# RCU_PCB.net
KiCad netlist of a schematic drawn in EAGLE
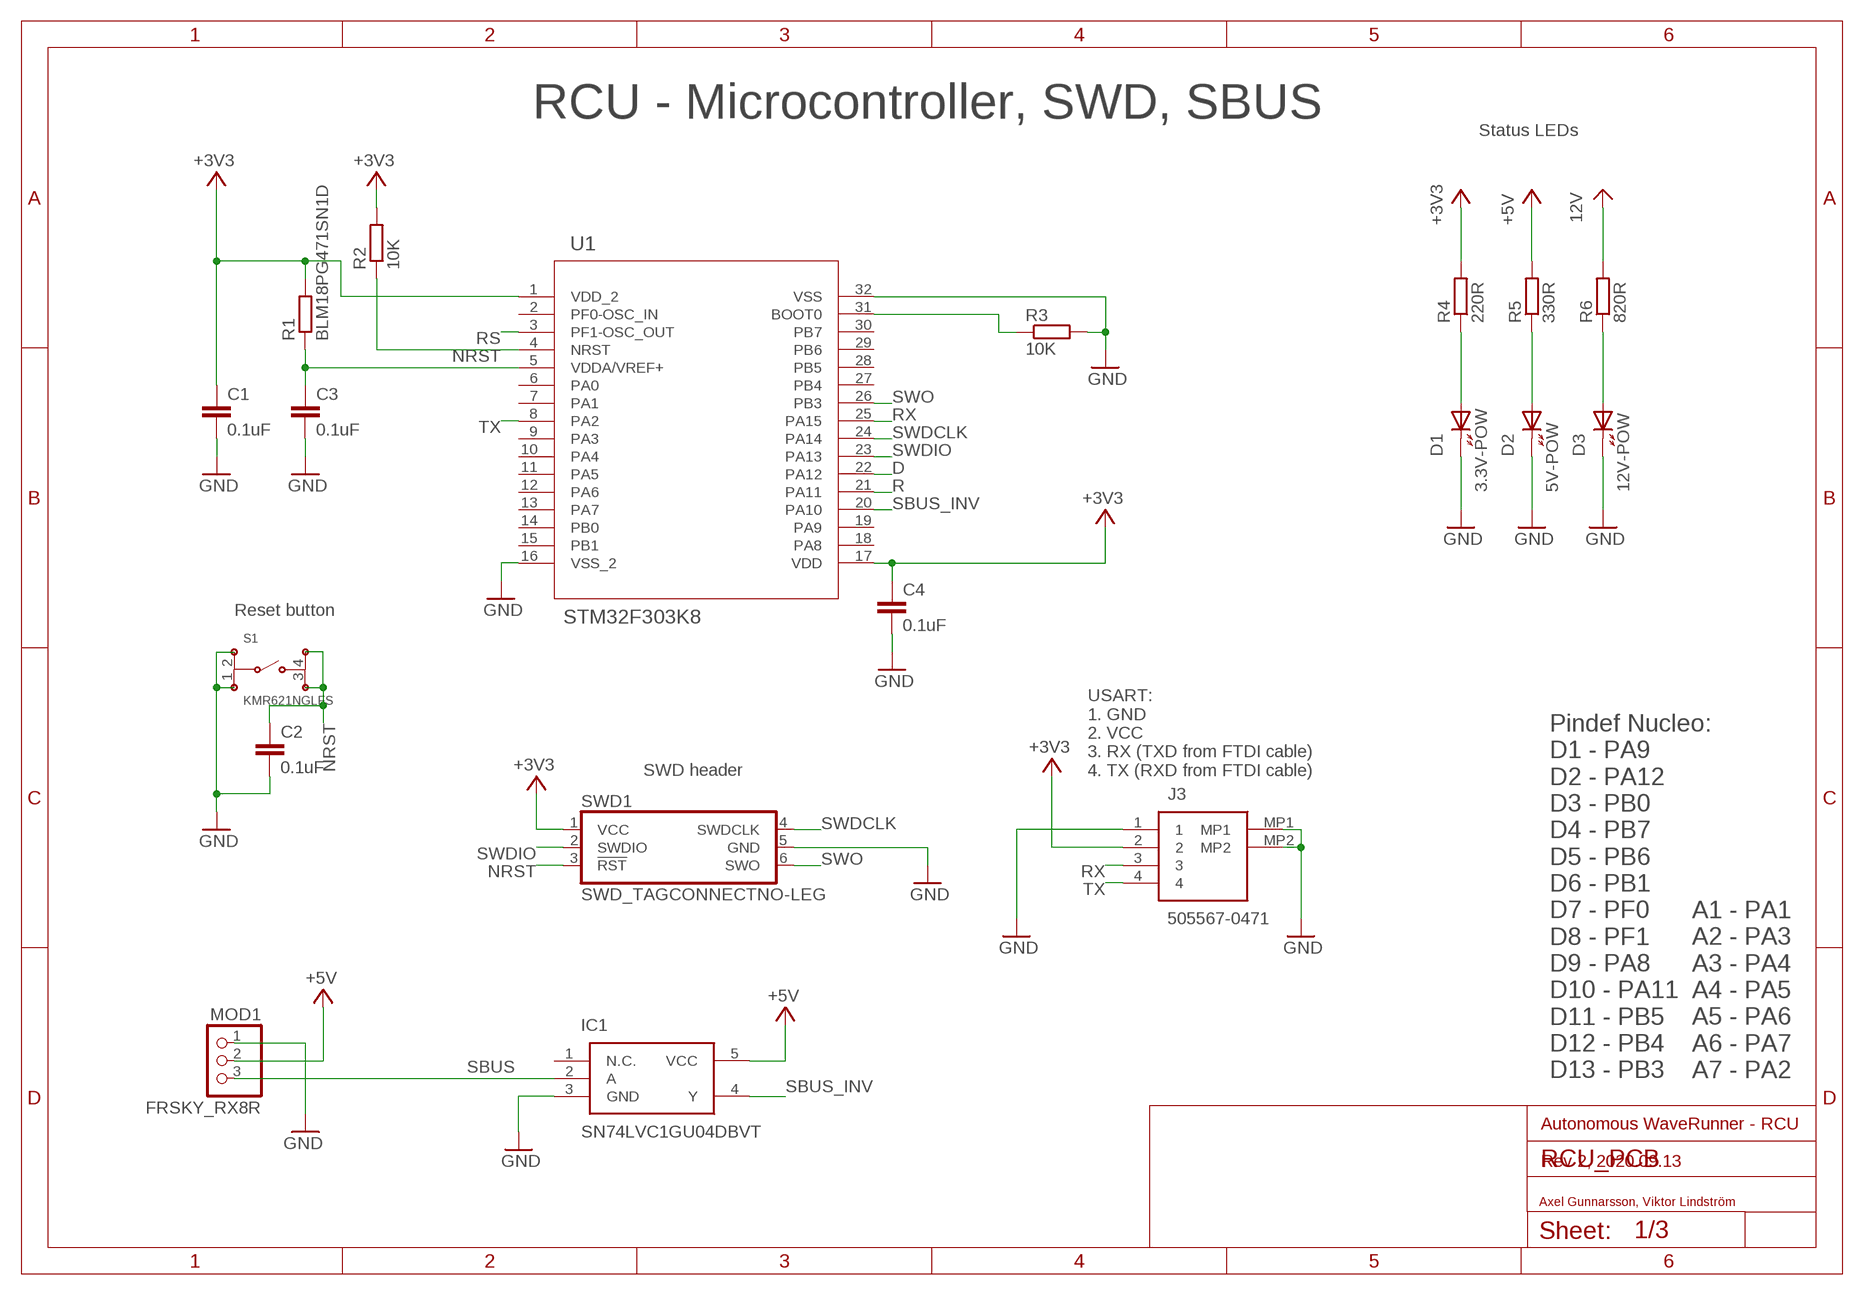
[diagram p0: schematic, sheet 1]
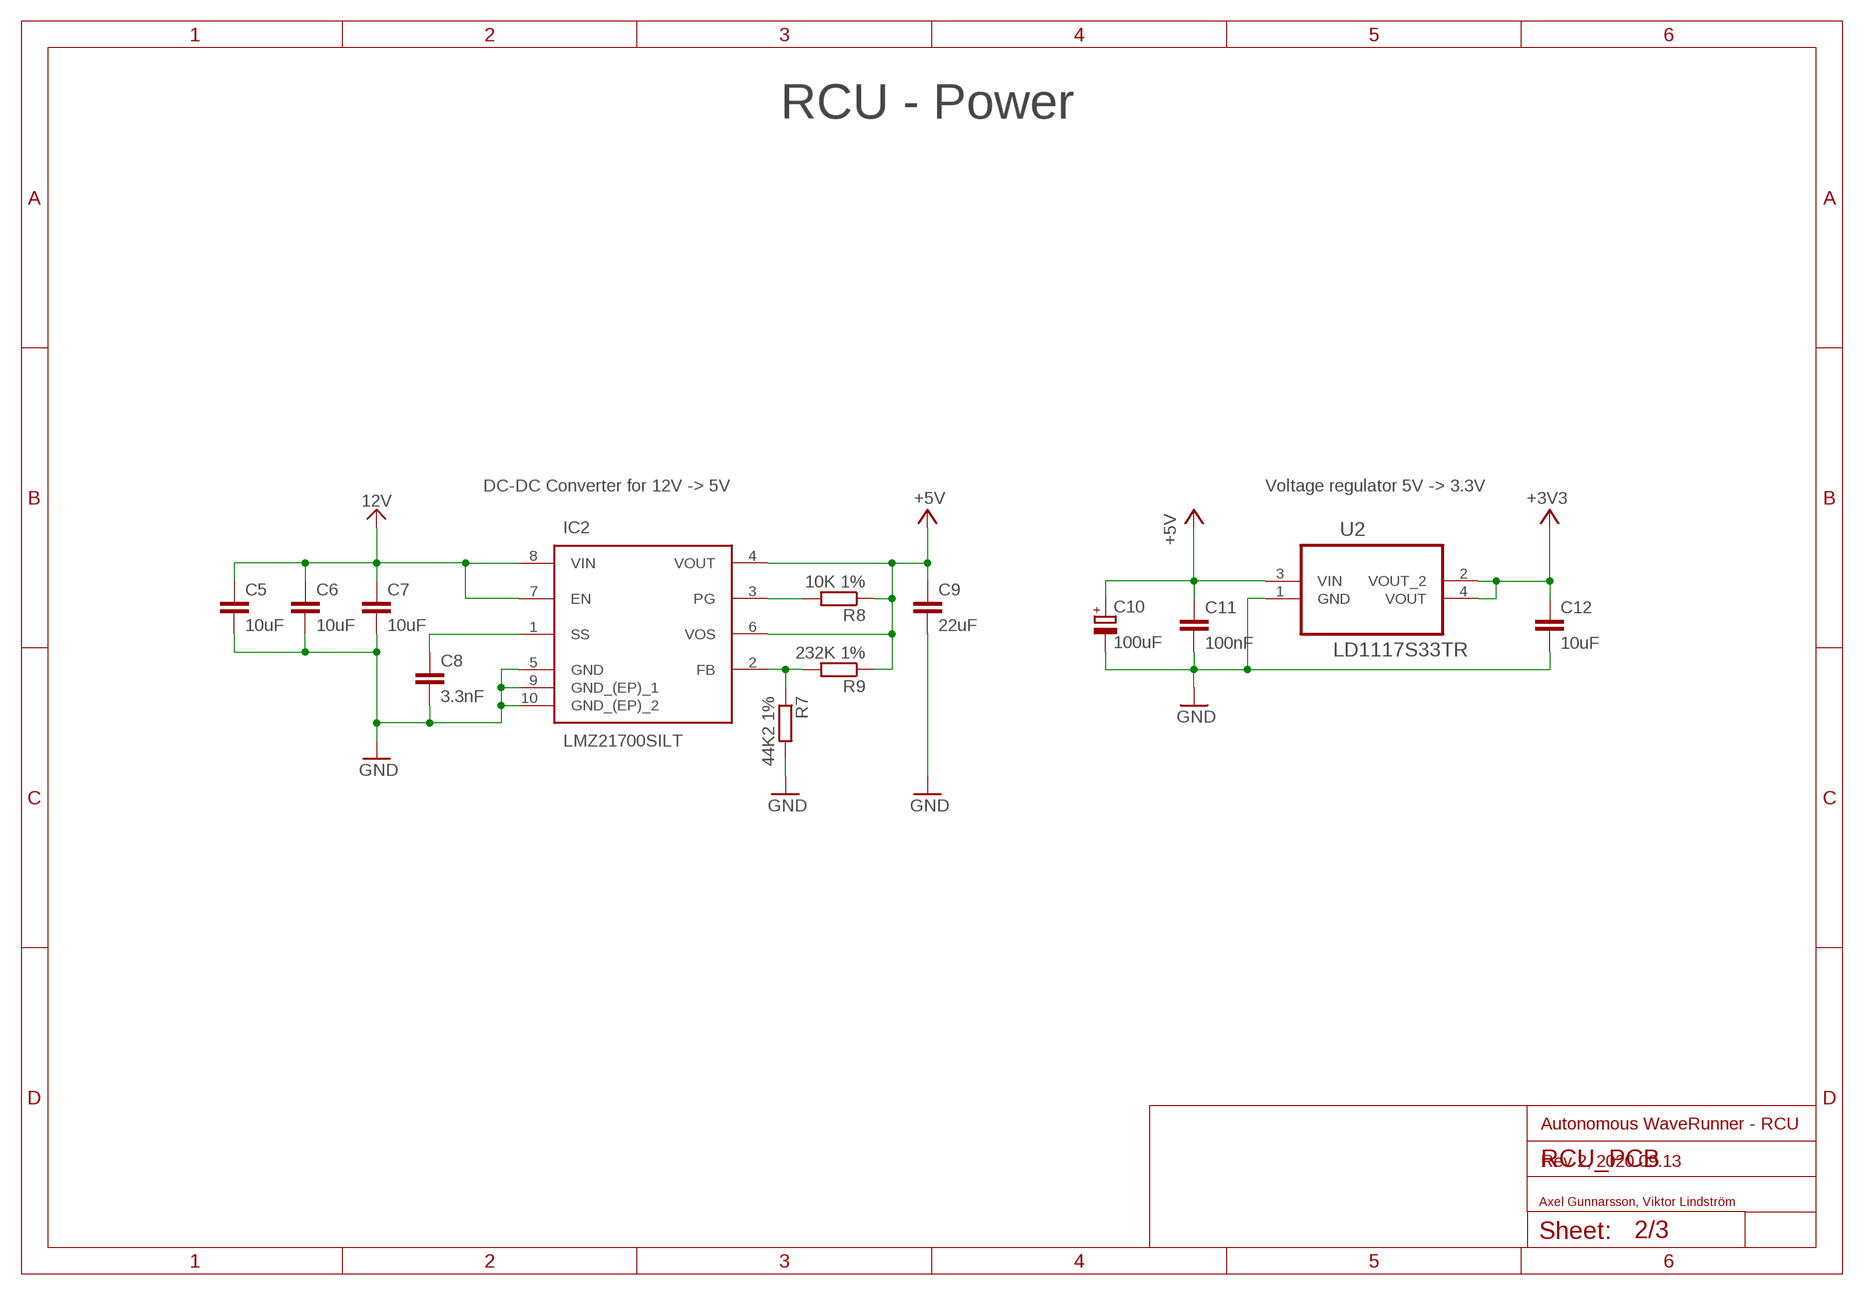
[diagram p1: schematic, sheet 2]
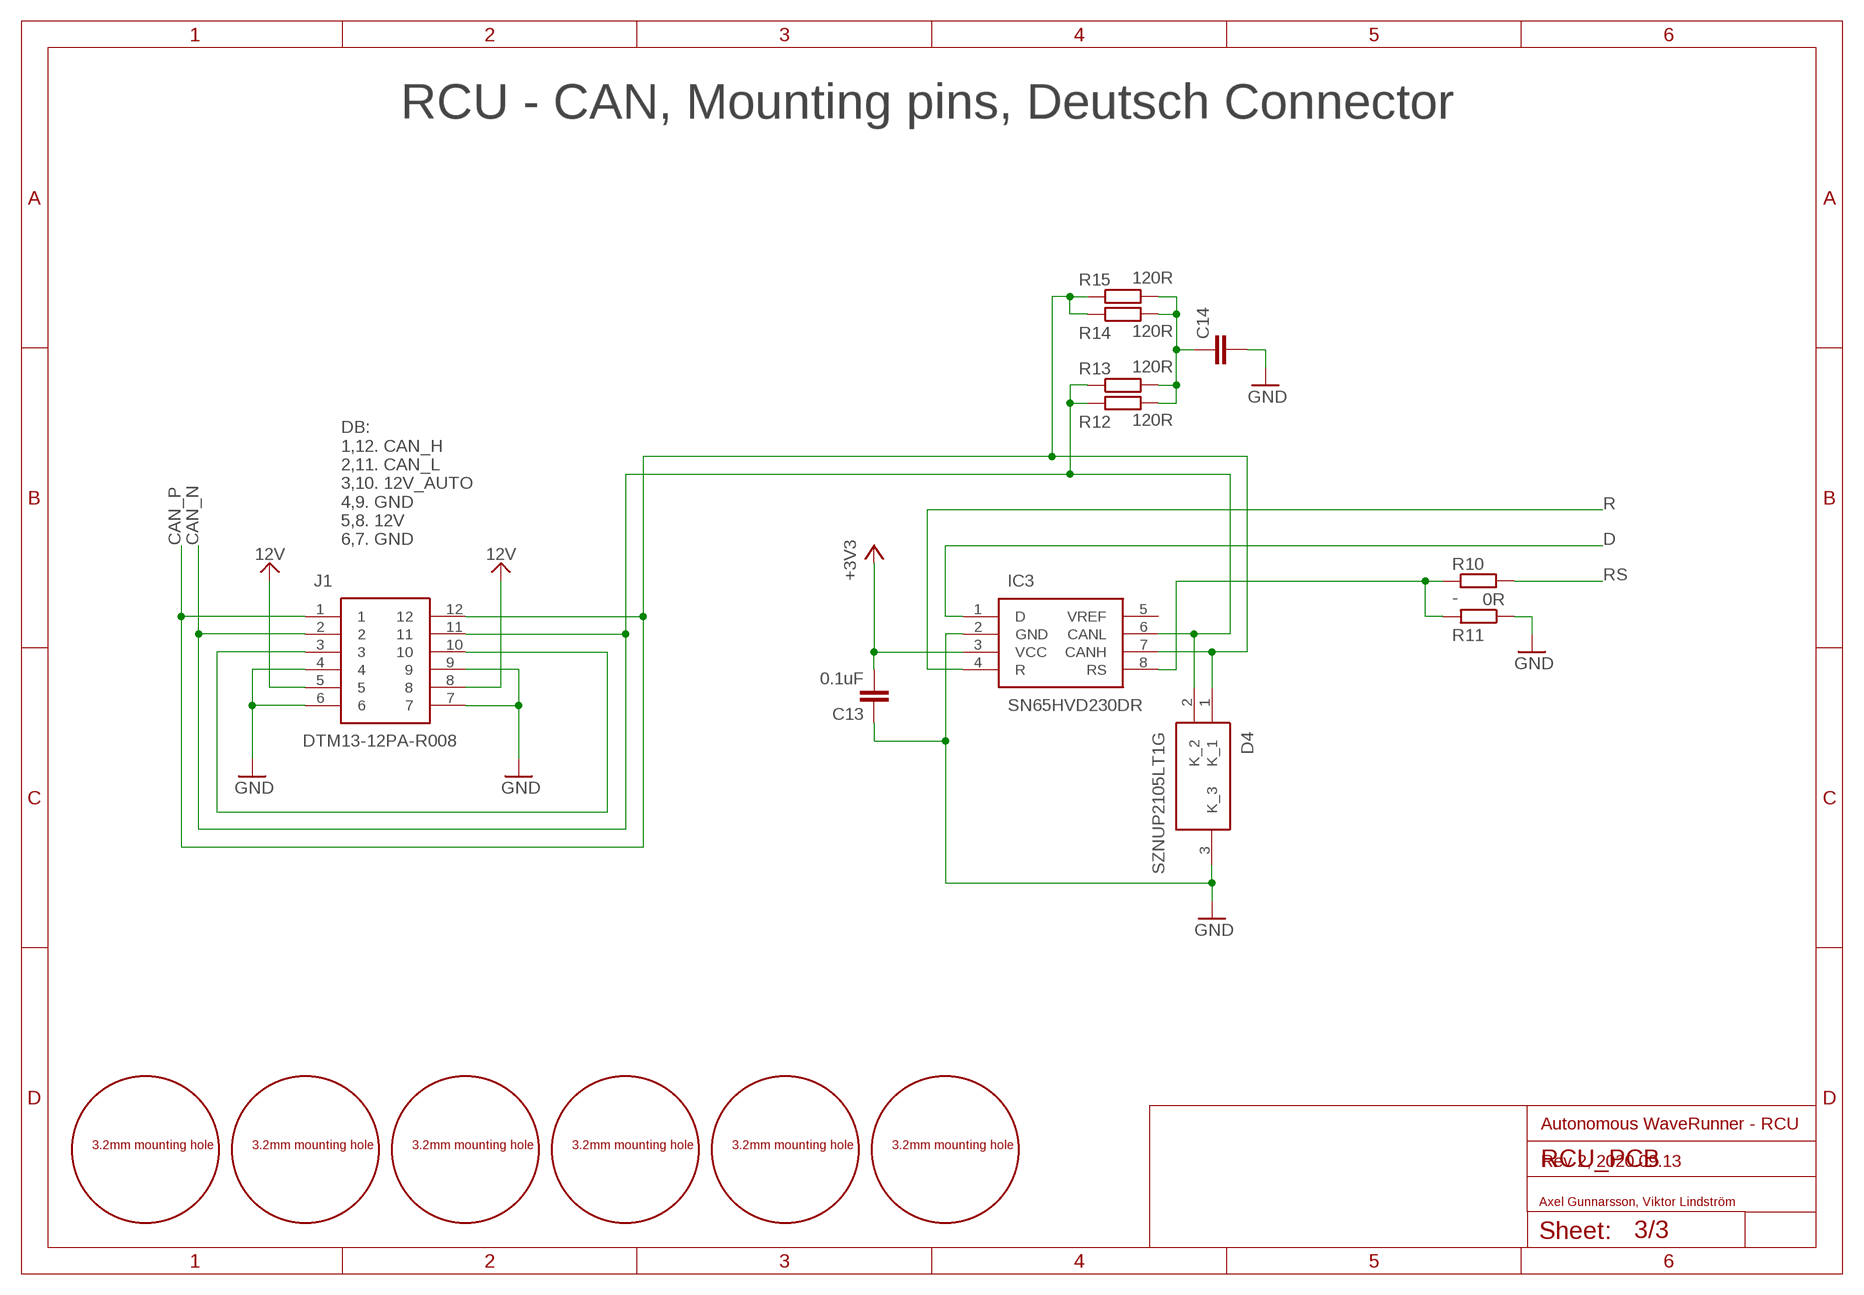
[diagram p2: schematic, sheet 3]

(export (version "E")
  (design (tool "Eeschema 10.0.6"))
  (components
    (comp (ref "C13")
      (value "0.1uF")
      (footprint "eagle-import:C0603")
      (libsource (lib "eagle-import") (part "C0603"))
    )
    (comp (ref "C14")
      (value "C0805")
      (footprint "eagle-import:C0805")
      (libsource (lib "eagle-import") (part "C0805"))
    )
    (comp (ref "D4")
      (value "SZNUP2105LT1G")
      (footprint "eagle-import:SOT96P237X111-3N")
      (fields (field (name "MOUSER_PART_NUMBER") "863-SZNUP2105LT1G"))
      (libsource (lib "eagle-import") (part "SZNUP2105LT1G"))
    )
    (comp (ref "HOLE1")
      (value "M3_MOUNTING_HOLE")
      (footprint "eagle-import:M3_MOUNTING_HOLE")
      (libsource (lib "eagle-import") (part "M3_MOUNTING_HOLE"))
    )
    (comp (ref "HOLE2")
      (value "M3_MOUNTING_HOLE")
      (footprint "eagle-import:M3_MOUNTING_HOLE")
      (libsource (lib "eagle-import") (part "M3_MOUNTING_HOLE"))
    )
    (comp (ref "HOLE3")
      (value "M3_MOUNTING_HOLE")
      (footprint "eagle-import:M3_MOUNTING_HOLE")
      (libsource (lib "eagle-import") (part "M3_MOUNTING_HOLE"))
    )
    (comp (ref "HOLE4")
      (value "M3_MOUNTING_HOLE")
      (footprint "eagle-import:M3_MOUNTING_HOLE")
      (libsource (lib "eagle-import") (part "M3_MOUNTING_HOLE"))
    )
    (comp (ref "HOLE5")
      (value "M3_MOUNTING_HOLE")
      (footprint "eagle-import:M3_MOUNTING_HOLE")
      (fields (field (name "SPICEPREFIX") "X"))
      (libsource (lib "eagle-import") (part "M3_MOUNTING_HOLE"))
    )
    (comp (ref "HOLE6")
      (value "M3_MOUNTING_HOLE")
      (footprint "eagle-import:M3_MOUNTING_HOLE")
      (fields (field (name "SPICEPREFIX") "X"))
      (libsource (lib "eagle-import") (part "M3_MOUNTING_HOLE"))
    )
    (comp (ref "IC3")
      (value "SN65HVD230DR")
      (footprint "eagle-import:SOT127P600X175-8N")
      (fields (field (name "MOUSER_PART_NUMBER") "595-SN65HVD230DR"))
      (libsource (lib "eagle-import") (part "SN65HVD230DR"))
    )
    (comp (ref "J1")
      (value "DTM13-12PA-R008")
      (footprint "eagle-import:DTM1312PAR008")
      (fields (field (name "RS_PART_NUMBER") "7242563"))
      (libsource (lib "eagle-import") (part "DTM13-12PA-R008"))
    )
    (comp (ref "R10")
      (value "-")
      (footprint "eagle-import:R0603")
      (libsource (lib "eagle-import") (part "R0603"))
    )
    (comp (ref "R11")
      (value "0R")
      (footprint "eagle-import:R0603")
      (libsource (lib "eagle-import") (part "R0603"))
    )
    (comp (ref "R12")
      (value "120R")
      (footprint "eagle-import:R1210")
      (libsource (lib "eagle-import") (part "R-EU_R1210"))
    )
    (comp (ref "R13")
      (value "120R")
      (footprint "eagle-import:R1210")
      (libsource (lib "eagle-import") (part "R-EU_R1210"))
    )
    (comp (ref "R14")
      (value "120R")
      (footprint "eagle-import:R1210")
      (libsource (lib "eagle-import") (part "R-EU_R1210"))
    )
    (comp (ref "R15")
      (value "120R")
      (footprint "eagle-import:R1210")
      (libsource (lib "eagle-import") (part "R-EU_R1210"))
    )
    (comp (ref "C1")
      (value "0.1uF")
      (footprint "eagle-import:C0603")
      (libsource (lib "eagle-import") (part "C0603"))
    )
    (comp (ref "C2")
      (value "0.1uF")
      (footprint "eagle-import:C0603")
      (libsource (lib "eagle-import") (part "C0603"))
    )
    (comp (ref "C3")
      (value "0.1uF")
      (footprint "eagle-import:C0603")
      (libsource (lib "eagle-import") (part "C0603"))
    )
    (comp (ref "C4")
      (value "0.1uF")
      (footprint "eagle-import:C0603")
      (libsource (lib "eagle-import") (part "C0603"))
    )
    (comp (ref "D1")
      (value "3.3V-POW")
      (footprint "eagle-import:CHIP-LED0805")
      (libsource (lib "eagle-import") (part "CHIP-LED0805"))
    )
    (comp (ref "D2")
      (value "5V-POW")
      (footprint "eagle-import:CHIP-LED0805")
      (libsource (lib "eagle-import") (part "CHIP-LED0805"))
    )
    (comp (ref "D3")
      (value "12V-POW")
      (footprint "eagle-import:CHIP-LED0805")
      (libsource (lib "eagle-import") (part "CHIP-LED0805"))
    )
    (comp (ref "IC1")
      (value "SN74LVC1GU04DBVT")
      (footprint "eagle-import:SOT95P280X145-5N")
      (fields (field (name "RS_PART_NUMBER") "7968253P"))
      (libsource (lib "eagle-import") (part "SN74LVC1GU04DBVT"))
    )
    (comp (ref "J3")
      (value "505567-0471")
      (footprint "eagle-import:5055680471")
      (libsource (lib "eagle-import") (part "505567-0471"))
    )
    (comp (ref "MOD1")
      (value "FRSKY_RX8R")
      (footprint "eagle-import:FRSKY_RX8R")
      (libsource (lib "eagle-import") (part "FRSKY_RX8R"))
    )
    (comp (ref "R1")
      (value "BLM18PG471SN1D")
      (footprint "eagle-import:R0603")
      (libsource (lib "eagle-import") (part "R0603"))
    )
    (comp (ref "R2")
      (value "10K")
      (footprint "eagle-import:R0603")
      (libsource (lib "eagle-import") (part "R0603"))
    )
    (comp (ref "R3")
      (value "10K")
      (footprint "eagle-import:R0603")
      (libsource (lib "eagle-import") (part "R0603"))
    )
    (comp (ref "R4")
      (value "220R")
      (footprint "eagle-import:R0603")
      (libsource (lib "eagle-import") (part "R0603"))
    )
    (comp (ref "R5")
      (value "330R")
      (footprint "eagle-import:R0603")
      (libsource (lib "eagle-import") (part "R0603"))
    )
    (comp (ref "R6")
      (value "820R")
      (footprint "eagle-import:R0603")
      (libsource (lib "eagle-import") (part "R0603"))
    )
    (comp (ref "S1")
      (value "KMR621NGLFS")
      (footprint "eagle-import:KMR621NGLFS")
      (libsource (lib "eagle-import") (part "KMR621NGLFS"))
    )
    (comp (ref "SWD1")
      (value "SWD_TAGCONNECTNO-LEG")
      (footprint "eagle-import:TC2030-IDC-NL")
      (libsource (lib "eagle-import") (part "SWD_TAGCONNECTNO-LEG"))
    )
    (comp (ref "U1")
      (value "STM32F303K8")
      (footprint "eagle-import:LQFP-32")
      (fields (field (name "MANUFACTURER_PART_NUMBER") "stm32f303_334kxt"))
      (libsource (lib "eagle-import") (part "STM32F303K8"))
    )
    (comp (ref "C5")
      (value "10uF")
      (footprint "eagle-import:C1206")
      (libsource (lib "eagle-import") (part "C1206"))
    )
    (comp (ref "C6")
      (value "10uF")
      (footprint "eagle-import:C1206")
      (libsource (lib "eagle-import") (part "C1206"))
    )
    (comp (ref "C7")
      (value "10uF")
      (footprint "eagle-import:C1206")
      (libsource (lib "eagle-import") (part "C1206"))
    )
    (comp (ref "C8")
      (value "3.3nF")
      (footprint "eagle-import:C0603")
      (libsource (lib "eagle-import") (part "C0603"))
    )
    (comp (ref "C9")
      (value "22uF")
      (footprint "eagle-import:C0805")
      (libsource (lib "eagle-import") (part "C0805"))
    )
    (comp (ref "C10")
      (value "100uF")
      (footprint "eagle-import:PANASONIC_C")
      (libsource (lib "eagle-import") (part "PANASONIC_C"))
    )
    (comp (ref "C11")
      (value "100nF")
      (footprint "eagle-import:C0603")
      (libsource (lib "eagle-import") (part "C0603"))
    )
    (comp (ref "C12")
      (value "10uF")
      (footprint "eagle-import:C0805")
      (libsource (lib "eagle-import") (part "C0805"))
    )
    (comp (ref "IC2")
      (value "LMZ21700SILT")
      (footprint "eagle-import:SIL0008E")
      (fields (field (name "RS_PART_NUMBER") "9009750P"))
      (libsource (lib "eagle-import") (part "LMZ21700SILT"))
    )
    (comp (ref "R7")
      (value "44K2 1%")
      (footprint "eagle-import:R0603")
      (libsource (lib "eagle-import") (part "R0603"))
    )
    (comp (ref "R8")
      (value "10K 1%")
      (footprint "eagle-import:R0603")
      (libsource (lib "eagle-import") (part "R0603"))
    )
    (comp (ref "R9")
      (value "232K 1%")
      (footprint "eagle-import:R0603")
      (libsource (lib "eagle-import") (part "R0603"))
    )
    (comp (ref "U2")
      (value "LD1117S33TR")
      (footprint "eagle-import:SOT230P700X180-4N")
      (libsource (lib "eagle-import") (part "LD1117S33TR"))
    )
  )
  (nets
    (net (code "1") (name "+3V3") (class "Default")
      (node (ref "C1") (pin "1") (pinfunction "1_1") (pintype "passive"))
      (node (ref "C12") (pin "1") (pinfunction "1_1") (pintype "passive"))
      (node (ref "C13") (pin "2") (pinfunction "2_2") (pintype "passive"))
      (node (ref "C4") (pin "1") (pinfunction "1_1") (pintype "passive"))
      (node (ref "IC3") (pin "3") (pinfunction "VCC_3") (pintype "bidirectional"))
      (node (ref "J3") (pin "2") (pinfunction "2_2") (pintype "bidirectional"))
      (node (ref "R1") (pin "2") (pinfunction "2_2") (pintype "passive"))
      (node (ref "R2") (pin "2") (pinfunction "2_2") (pintype "passive"))
      (node (ref "R4") (pin "2") (pinfunction "2_2") (pintype "passive"))
      (node (ref "SWD1") (pin "1") (pinfunction "VCC_1") (pintype "passive"))
      (node (ref "U1") (pin "1") (pinfunction "VDD_2_1") (pintype "power_in"))
      (node (ref "U1") (pin "17") (pinfunction "VDD_17") (pintype "power_in"))
      (node (ref "U2") (pin "2") (pinfunction "VOUT_2_2") (pintype "output"))
      (node (ref "U2") (pin "4") (pinfunction "VOUT_4") (pintype "output"))
    )
    (net (code "2") (name "+5V") (class "Default")
      (node (ref "C10") (pin "+") (pinfunction "+_+") (pintype "passive"))
      (node (ref "C11") (pin "1") (pinfunction "1_1") (pintype "passive"))
      (node (ref "C9") (pin "1") (pinfunction "1_1") (pintype "passive"))
      (node (ref "IC1") (pin "5") (pinfunction "VCC_5") (pintype "bidirectional"))
      (node (ref "IC2") (pin "4") (pinfunction "VOUT_4") (pintype "output"))
      (node (ref "IC2") (pin "6") (pinfunction "VOS_6") (pintype "bidirectional"))
      (node (ref "MOD1") (pin "2") (pinfunction "2_2") (pintype "passive"))
      (node (ref "R5") (pin "2") (pinfunction "2_2") (pintype "passive"))
      (node (ref "R8") (pin "1") (pinfunction "1_1") (pintype "passive"))
      (node (ref "R9") (pin "1") (pinfunction "1_1") (pintype "passive"))
      (node (ref "U2") (pin "3") (pinfunction "VIN_3") (pintype "input"))
    )
    (net (code "3") (name "12V") (class "Default")
      (node (ref "C5") (pin "1") (pinfunction "1_1") (pintype "passive"))
      (node (ref "C6") (pin "1") (pinfunction "1_1") (pintype "passive"))
      (node (ref "C7") (pin "1") (pinfunction "1_1") (pintype "passive"))
      (node (ref "IC2") (pin "7") (pinfunction "EN_7") (pintype "bidirectional"))
      (node (ref "IC2") (pin "8") (pinfunction "VIN_8") (pintype "input"))
      (node (ref "J1") (pin "5") (pinfunction "5_5") (pintype "bidirectional"))
      (node (ref "J1") (pin "8") (pinfunction "8_8") (pintype "bidirectional"))
      (node (ref "R6") (pin "2") (pinfunction "2_2") (pintype "passive"))
    )
    (net (code "4") (name "CAN_N") (class "Default")
      (node (ref "D4") (pin "2") (pinfunction "K_2_2") (pintype "bidirectional"))
      (node (ref "IC3") (pin "6") (pinfunction "CANL_6") (pintype "bidirectional"))
      (node (ref "J1") (pin "11") (pinfunction "11_11") (pintype "bidirectional"))
      (node (ref "J1") (pin "2") (pinfunction "2_2") (pintype "bidirectional"))
      (node (ref "R12") (pin "1") (pinfunction "1_1") (pintype "passive"))
      (node (ref "R13") (pin "1") (pinfunction "1_1") (pintype "passive"))
    )
    (net (code "5") (name "CAN_P") (class "Default")
      (node (ref "D4") (pin "1") (pinfunction "K_1_1") (pintype "bidirectional"))
      (node (ref "IC3") (pin "7") (pinfunction "CANH_7") (pintype "bidirectional"))
      (node (ref "J1") (pin "1") (pinfunction "1_1") (pintype "bidirectional"))
      (node (ref "J1") (pin "12") (pinfunction "12_12") (pintype "bidirectional"))
      (node (ref "R14") (pin "1") (pinfunction "1_1") (pintype "passive"))
      (node (ref "R15") (pin "1") (pinfunction "1_1") (pintype "passive"))
    )
    (net (code "6") (name "D") (class "Default")
      (node (ref "IC3") (pin "1") (pinfunction "D_1") (pintype "bidirectional"))
      (node (ref "U1") (pin "22") (pinfunction "PA12_22") (pintype "bidirectional"))
    )
    (net (code "7") (name "GND") (class "Default")
      (node (ref "C1") (pin "2") (pinfunction "2_2") (pintype "passive"))
      (node (ref "C10") (pin "-") (pinfunction "-_-") (pintype "passive"))
      (node (ref "C11") (pin "2") (pinfunction "2_2") (pintype "passive"))
      (node (ref "C12") (pin "2") (pinfunction "2_2") (pintype "passive"))
      (node (ref "C13") (pin "1") (pinfunction "1_1") (pintype "passive"))
      (node (ref "C14") (pin "2") (pinfunction "2_2") (pintype "passive"))
      (node (ref "C2") (pin "2") (pinfunction "2_2") (pintype "passive"))
      (node (ref "C3") (pin "2") (pinfunction "2_2") (pintype "passive"))
      (node (ref "C4") (pin "2") (pinfunction "2_2") (pintype "passive"))
      (node (ref "C5") (pin "2") (pinfunction "2_2") (pintype "passive"))
      (node (ref "C6") (pin "2") (pinfunction "2_2") (pintype "passive"))
      (node (ref "C7") (pin "2") (pinfunction "2_2") (pintype "passive"))
      (node (ref "C8") (pin "2") (pinfunction "2_2") (pintype "passive"))
      (node (ref "C9") (pin "2") (pinfunction "2_2") (pintype "passive"))
      (node (ref "D1") (pin "C") (pinfunction "K_C") (pintype "passive"))
      (node (ref "D2") (pin "C") (pinfunction "K_C") (pintype "passive"))
      (node (ref "D3") (pin "C") (pinfunction "K_C") (pintype "passive"))
      (node (ref "D4") (pin "3") (pinfunction "K_3_3") (pintype "bidirectional"))
      (node (ref "IC1") (pin "3") (pinfunction "GND_3") (pintype "bidirectional"))
      (node (ref "IC2") (pin "10") (pinfunction "GND_(EP)_2_10") (pintype "power_in"))
      (node (ref "IC2") (pin "5") (pinfunction "GND_5") (pintype "power_in"))
      (node (ref "IC2") (pin "9") (pinfunction "GND_(EP)_1_9") (pintype "power_in"))
      (node (ref "IC3") (pin "2") (pinfunction "GND_2") (pintype "bidirectional"))
      (node (ref "J1") (pin "4") (pinfunction "4_4") (pintype "bidirectional"))
      (node (ref "J1") (pin "6") (pinfunction "6_6") (pintype "bidirectional"))
      (node (ref "J1") (pin "7") (pinfunction "7_7") (pintype "bidirectional"))
      (node (ref "J1") (pin "9") (pinfunction "9_9") (pintype "bidirectional"))
      (node (ref "J3") (pin "1") (pinfunction "1_1") (pintype "bidirectional"))
      (node (ref "J3") (pin "MP1") (pinfunction "MP1_MP1") (pintype "bidirectional"))
      (node (ref "J3") (pin "MP2") (pinfunction "MP2_MP2") (pintype "bidirectional"))
      (node (ref "MOD1") (pin "1") (pinfunction "1_1") (pintype "passive"))
      (node (ref "R11") (pin "1") (pinfunction "1_1") (pintype "passive"))
      (node (ref "R3") (pin "2") (pinfunction "2_2") (pintype "passive"))
      (node (ref "R7") (pin "2") (pinfunction "2_2") (pintype "passive"))
      (node (ref "S1") (pin "1") (pinfunction "1_1") (pintype "bidirectional"))
      (node (ref "S1") (pin "2") (pinfunction "2_2") (pintype "bidirectional"))
      (node (ref "SWD1") (pin "5") (pinfunction "GND_5") (pintype "passive"))
      (node (ref "U1") (pin "16") (pinfunction "VSS_2_16") (pintype "power_in"))
      (node (ref "U1") (pin "32") (pinfunction "VSS_32") (pintype "power_in"))
      (node (ref "U2") (pin "1") (pinfunction "GND_1") (pintype "passive"))
    )
    (net (code "8") (name "NRST") (class "Default")
      (node (ref "C2") (pin "1") (pinfunction "1_1") (pintype "passive"))
      (node (ref "R2") (pin "1") (pinfunction "1_1") (pintype "passive"))
      (node (ref "S1") (pin "3") (pinfunction "3_3") (pintype "bidirectional"))
      (node (ref "S1") (pin "4") (pinfunction "4_4") (pintype "bidirectional"))
      (node (ref "SWD1") (pin "3") (pinfunction "~{RST}_3") (pintype "passive"))
      (node (ref "U1") (pin "4") (pinfunction "NRST_4") (pintype "bidirectional"))
    )
    (net (code "9") (name "Net-(C14-Pad1)") (class "Default")
      (node (ref "C14") (pin "1") (pinfunction "1_1") (pintype "passive"))
      (node (ref "R12") (pin "2") (pinfunction "2_2") (pintype "passive"))
      (node (ref "R13") (pin "2") (pinfunction "2_2") (pintype "passive"))
      (node (ref "R14") (pin "2") (pinfunction "2_2") (pintype "passive"))
      (node (ref "R15") (pin "2") (pinfunction "2_2") (pintype "passive"))
    )
    (net (code "10") (name "Net-(D1-PadA)") (class "Default")
      (node (ref "D1") (pin "A") (pinfunction "A_A") (pintype "passive"))
      (node (ref "R4") (pin "1") (pinfunction "1_1") (pintype "passive"))
    )
    (net (code "11") (name "Net-(D2-PadA)") (class "Default")
      (node (ref "D2") (pin "A") (pinfunction "A_A") (pintype "passive"))
      (node (ref "R5") (pin "1") (pinfunction "1_1") (pintype "passive"))
    )
    (net (code "12") (name "Net-(D3-PadA)") (class "Default")
      (node (ref "D3") (pin "A") (pinfunction "A_A") (pintype "passive"))
      (node (ref "R6") (pin "1") (pinfunction "1_1") (pintype "passive"))
    )
    (net (code "13") (name "Net-(IC2-FB)") (class "Default")
      (node (ref "IC2") (pin "2") (pinfunction "FB_2") (pintype "bidirectional"))
      (node (ref "R7") (pin "1") (pinfunction "1_1") (pintype "passive"))
      (node (ref "R9") (pin "2") (pinfunction "2_2") (pintype "passive"))
    )
    (net (code "14") (name "Net-(IC2-PG)") (class "Default")
      (node (ref "IC2") (pin "3") (pinfunction "PG_3") (pintype "bidirectional"))
      (node (ref "R8") (pin "2") (pinfunction "2_2") (pintype "passive"))
    )
    (net (code "15") (name "Net-(IC2-SS)") (class "Default")
      (node (ref "C8") (pin "1") (pinfunction "1_1") (pintype "passive"))
      (node (ref "IC2") (pin "1") (pinfunction "SS_1") (pintype "bidirectional"))
    )
    (net (code "16") (name "Net-(IC3-RS)") (class "Default")
      (node (ref "IC3") (pin "8") (pinfunction "RS_8") (pintype "bidirectional"))
      (node (ref "R10") (pin "1") (pinfunction "1_1") (pintype "passive"))
      (node (ref "R11") (pin "2") (pinfunction "2_2") (pintype "passive"))
    )
    (net (code "17") (name "Net-(J1-Pad10)") (class "Default")
      (node (ref "J1") (pin "10") (pinfunction "10_10") (pintype "bidirectional"))
      (node (ref "J1") (pin "3") (pinfunction "3_3") (pintype "bidirectional"))
    )
    (net (code "18") (name "Net-(U1-BOOT0)") (class "Default")
      (node (ref "R3") (pin "1") (pinfunction "1_1") (pintype "passive"))
      (node (ref "U1") (pin "31") (pinfunction "BOOT0_31") (pintype "input"))
    )
    (net (code "19") (name "Net-(U1-VDDA{slash}VREF+)") (class "Default")
      (node (ref "C3") (pin "1") (pinfunction "1_1") (pintype "passive"))
      (node (ref "R1") (pin "1") (pinfunction "1_1") (pintype "passive"))
      (node (ref "U1") (pin "5") (pinfunction "VDDA/VREF+_5") (pintype "power_in"))
    )
    (net (code "20") (name "R") (class "Default")
      (node (ref "IC3") (pin "4") (pinfunction "R_4") (pintype "bidirectional"))
      (node (ref "U1") (pin "21") (pinfunction "PA11_21") (pintype "bidirectional"))
    )
    (net (code "21") (name "RS") (class "Default")
      (node (ref "R10") (pin "2") (pinfunction "2_2") (pintype "passive"))
      (node (ref "U1") (pin "3") (pinfunction "PF1-OSC_OUT_3") (pintype "bidirectional"))
    )
    (net (code "22") (name "RX") (class "Default")
      (node (ref "J3") (pin "3") (pinfunction "3_3") (pintype "bidirectional"))
      (node (ref "U1") (pin "25") (pinfunction "PA15_25") (pintype "bidirectional"))
    )
    (net (code "23") (name "SBUS") (class "Default")
      (node (ref "IC1") (pin "2") (pinfunction "A_2") (pintype "bidirectional"))
      (node (ref "MOD1") (pin "3") (pinfunction "3_3") (pintype "passive"))
    )
    (net (code "24") (name "SBUS_INV") (class "Default")
      (node (ref "IC1") (pin "4") (pinfunction "Y_4") (pintype "bidirectional"))
      (node (ref "U1") (pin "20") (pinfunction "PA10_20") (pintype "bidirectional"))
    )
    (net (code "25") (name "SWDCLK") (class "Default")
      (node (ref "SWD1") (pin "4") (pinfunction "SWDCLK_4") (pintype "passive"))
      (node (ref "U1") (pin "24") (pinfunction "PA14_24") (pintype "bidirectional"))
    )
    (net (code "26") (name "SWDIO") (class "Default")
      (node (ref "SWD1") (pin "2") (pinfunction "SWDIO_2") (pintype "passive"))
      (node (ref "U1") (pin "23") (pinfunction "PA13_23") (pintype "bidirectional"))
    )
    (net (code "27") (name "SWO") (class "Default")
      (node (ref "SWD1") (pin "6") (pinfunction "SWO_6") (pintype "passive"))
      (node (ref "U1") (pin "26") (pinfunction "PB3_26") (pintype "bidirectional"))
    )
    (net (code "28") (name "TX") (class "Default")
      (node (ref "J3") (pin "4") (pinfunction "4_4") (pintype "bidirectional"))
      (node (ref "U1") (pin "8") (pinfunction "PA2_8") (pintype "bidirectional"))
    )
    (net (code "29") (name "unconnected-(IC1-N.C.-Pad1)") (class "Default")
      (node (ref "IC1") (pin "1") (pinfunction "N.C._1") (pintype "no_connect"))
    )
    (net (code "30") (name "unconnected-(IC3-VREF-Pad5)") (class "Default")
      (node (ref "IC3") (pin "5") (pinfunction "VREF_5") (pintype "bidirectional"))
    )
    (net (code "31") (name "unconnected-(U1-PA0-Pad6)") (class "Default")
      (node (ref "U1") (pin "6") (pinfunction "PA0_6") (pintype "bidirectional"))
    )
    (net (code "32") (name "unconnected-(U1-PA1-Pad7)") (class "Default")
      (node (ref "U1") (pin "7") (pinfunction "PA1_7") (pintype "bidirectional"))
    )
    (net (code "33") (name "unconnected-(U1-PA3-Pad9)") (class "Default")
      (node (ref "U1") (pin "9") (pinfunction "PA3_9") (pintype "bidirectional"))
    )
    (net (code "34") (name "unconnected-(U1-PA4-Pad10)") (class "Default")
      (node (ref "U1") (pin "10") (pinfunction "PA4_10") (pintype "bidirectional"))
    )
    (net (code "35") (name "unconnected-(U1-PA5-Pad11)") (class "Default")
      (node (ref "U1") (pin "11") (pinfunction "PA5_11") (pintype "bidirectional"))
    )
    (net (code "36") (name "unconnected-(U1-PA6-Pad12)") (class "Default")
      (node (ref "U1") (pin "12") (pinfunction "PA6_12") (pintype "bidirectional"))
    )
    (net (code "37") (name "unconnected-(U1-PA7-Pad13)") (class "Default")
      (node (ref "U1") (pin "13") (pinfunction "PA7_13") (pintype "bidirectional"))
    )
    (net (code "38") (name "unconnected-(U1-PA8-Pad18)") (class "Default")
      (node (ref "U1") (pin "18") (pinfunction "PA8_18") (pintype "bidirectional"))
    )
    (net (code "39") (name "unconnected-(U1-PA9-Pad19)") (class "Default")
      (node (ref "U1") (pin "19") (pinfunction "PA9_19") (pintype "bidirectional"))
    )
    (net (code "40") (name "unconnected-(U1-PB0-Pad14)") (class "Default")
      (node (ref "U1") (pin "14") (pinfunction "PB0_14") (pintype "bidirectional"))
    )
    (net (code "41") (name "unconnected-(U1-PB1-Pad15)") (class "Default")
      (node (ref "U1") (pin "15") (pinfunction "PB1_15") (pintype "bidirectional"))
    )
    (net (code "42") (name "unconnected-(U1-PB4-Pad27)") (class "Default")
      (node (ref "U1") (pin "27") (pinfunction "PB4_27") (pintype "bidirectional"))
    )
    (net (code "43") (name "unconnected-(U1-PB5-Pad28)") (class "Default")
      (node (ref "U1") (pin "28") (pinfunction "PB5_28") (pintype "bidirectional"))
    )
    (net (code "44") (name "unconnected-(U1-PB6-Pad29)") (class "Default")
      (node (ref "U1") (pin "29") (pinfunction "PB6_29") (pintype "bidirectional"))
    )
    (net (code "45") (name "unconnected-(U1-PB7-Pad30)") (class "Default")
      (node (ref "U1") (pin "30") (pinfunction "PB7_30") (pintype "bidirectional"))
    )
    (net (code "46") (name "unconnected-(U1-PF0-OSC_IN-Pad2)") (class "Default")
      (node (ref "U1") (pin "2") (pinfunction "PF0-OSC_IN_2") (pintype "bidirectional"))
    )
  )
)
